# L293D.net
KiCad netlist of a schematic drawn in EAGLE
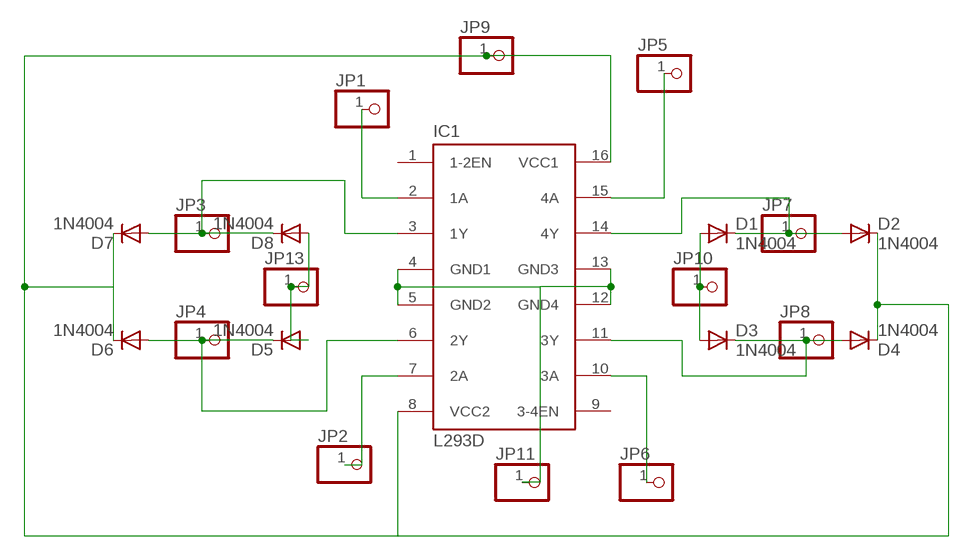
[diagram p0: schematic, sheet 1]

(export (version "E")
  (design (tool "Eeschema 10.0.6"))
  (components
    (comp (ref "D1")
      (value "1N4004")
      (footprint "eagle-import:DO41-10")
      (libsource (lib "eagle-import") (part "1N4004"))
    )
    (comp (ref "D2")
      (value "1N4004")
      (footprint "eagle-import:DO41-10")
      (libsource (lib "eagle-import") (part "1N4004"))
    )
    (comp (ref "D3")
      (value "1N4004")
      (footprint "eagle-import:DO41-10")
      (libsource (lib "eagle-import") (part "1N4004"))
    )
    (comp (ref "D4")
      (value "1N4004")
      (footprint "eagle-import:DO41-10")
      (libsource (lib "eagle-import") (part "1N4004"))
    )
    (comp (ref "D5")
      (value "1N4004")
      (footprint "eagle-import:DO41-10")
      (libsource (lib "eagle-import") (part "1N4004"))
    )
    (comp (ref "D6")
      (value "1N4004")
      (footprint "eagle-import:DO41-10")
      (libsource (lib "eagle-import") (part "1N4004"))
    )
    (comp (ref "D7")
      (value "1N4004")
      (footprint "eagle-import:DO41-10")
      (libsource (lib "eagle-import") (part "1N4004"))
    )
    (comp (ref "D8")
      (value "1N4004")
      (footprint "eagle-import:DO41-10")
      (libsource (lib "eagle-import") (part "1N4004"))
    )
    (comp (ref "IC1")
      (value "L293D")
      (footprint "eagle-import:DIL16")
      (libsource (lib "eagle-import") (part "L293D"))
    )
    (comp (ref "JP1")
      (value "PINHD-1X1")
      (footprint "eagle-import:1X01")
      (libsource (lib "eagle-import") (part "PINHD-1X1"))
    )
    (comp (ref "JP2")
      (value "PINHD-1X1")
      (footprint "eagle-import:1X01")
      (libsource (lib "eagle-import") (part "PINHD-1X1"))
    )
    (comp (ref "JP3")
      (value "PINHD-1X1")
      (footprint "eagle-import:1X01")
      (libsource (lib "eagle-import") (part "PINHD-1X1"))
    )
    (comp (ref "JP4")
      (value "PINHD-1X1")
      (footprint "eagle-import:1X01")
      (libsource (lib "eagle-import") (part "PINHD-1X1"))
    )
    (comp (ref "JP5")
      (value "PINHD-1X1")
      (footprint "eagle-import:1X01")
      (libsource (lib "eagle-import") (part "PINHD-1X1"))
    )
    (comp (ref "JP6")
      (value "PINHD-1X1")
      (footprint "eagle-import:1X01")
      (libsource (lib "eagle-import") (part "PINHD-1X1"))
    )
    (comp (ref "JP7")
      (value "PINHD-1X1")
      (footprint "eagle-import:1X01")
      (libsource (lib "eagle-import") (part "PINHD-1X1"))
    )
    (comp (ref "JP8")
      (value "PINHD-1X1")
      (footprint "eagle-import:1X01")
      (libsource (lib "eagle-import") (part "PINHD-1X1"))
    )
    (comp (ref "JP9")
      (value "PINHD-1X1")
      (footprint "eagle-import:1X01")
      (libsource (lib "eagle-import") (part "PINHD-1X1"))
    )
    (comp (ref "JP10")
      (value "PINHD-1X1")
      (footprint "eagle-import:1X01")
      (libsource (lib "eagle-import") (part "PINHD-1X1"))
    )
    (comp (ref "JP11")
      (value "PINHD-1X1")
      (footprint "eagle-import:1X01")
      (libsource (lib "eagle-import") (part "PINHD-1X1"))
    )
    (comp (ref "JP13")
      (value "PINHD-1X1")
      (footprint "eagle-import:1X01")
      (libsource (lib "eagle-import") (part "PINHD-1X1"))
    )
  )
  (nets
    (net (code "1") (name "Net-(D1-PadA)") (class "Default")
      (node (ref "D1") (pin "A") (pinfunction "A_A") (pintype "passive"))
      (node (ref "D3") (pin "A") (pinfunction "A_A") (pintype "passive"))
      (node (ref "JP10") (pin "1") (pinfunction "1_1") (pintype "passive"))
    )
    (net (code "2") (name "Net-(D5-PadA)") (class "Default")
      (node (ref "D5") (pin "A") (pinfunction "A_A") (pintype "passive"))
      (node (ref "D8") (pin "A") (pinfunction "A_A") (pintype "passive"))
      (node (ref "JP13") (pin "1") (pinfunction "1_1") (pintype "passive"))
    )
    (net (code "3") (name "Net-(D6-PadC)") (class "Default")
      (node (ref "D6") (pin "C") (pinfunction "C_C") (pintype "passive"))
      (node (ref "D7") (pin "C") (pinfunction "C_C") (pintype "passive"))
    )
    (net (code "4") (name "Net-(IC1-1A)") (class "Default")
      (node (ref "IC1") (pin "2") (pinfunction "1A_2") (pintype "input"))
      (node (ref "JP1") (pin "1") (pinfunction "1_1") (pintype "passive"))
    )
    (net (code "5") (name "Net-(IC1-1Y)") (class "Default")
      (node (ref "D7") (pin "A") (pinfunction "A_A") (pintype "passive"))
      (node (ref "D8") (pin "C") (pinfunction "C_C") (pintype "passive"))
      (node (ref "IC1") (pin "3") (pinfunction "1Y_3") (pintype "output"))
      (node (ref "JP3") (pin "1") (pinfunction "1_1") (pintype "passive"))
    )
    (net (code "6") (name "Net-(IC1-2A)") (class "Default")
      (node (ref "IC1") (pin "7") (pinfunction "2A_7") (pintype "input"))
      (node (ref "JP2") (pin "1") (pinfunction "1_1") (pintype "passive"))
    )
    (net (code "7") (name "Net-(IC1-2Y)") (class "Default")
      (node (ref "D5") (pin "C") (pinfunction "C_C") (pintype "passive"))
      (node (ref "D6") (pin "A") (pinfunction "A_A") (pintype "passive"))
      (node (ref "IC1") (pin "6") (pinfunction "2Y_6") (pintype "output"))
      (node (ref "JP4") (pin "1") (pinfunction "1_1") (pintype "passive"))
    )
    (net (code "8") (name "Net-(IC1-3A)") (class "Default")
      (node (ref "IC1") (pin "10") (pinfunction "3A_10") (pintype "input"))
      (node (ref "JP6") (pin "1") (pinfunction "1_1") (pintype "passive"))
    )
    (net (code "9") (name "Net-(IC1-3Y)") (class "Default")
      (node (ref "D3") (pin "C") (pinfunction "C_C") (pintype "passive"))
      (node (ref "D4") (pin "A") (pinfunction "A_A") (pintype "passive"))
      (node (ref "IC1") (pin "11") (pinfunction "3Y_11") (pintype "output"))
      (node (ref "JP8") (pin "1") (pinfunction "1_1") (pintype "passive"))
    )
    (net (code "10") (name "Net-(IC1-4A)") (class "Default")
      (node (ref "IC1") (pin "15") (pinfunction "4A_15") (pintype "input"))
      (node (ref "JP5") (pin "1") (pinfunction "1_1") (pintype "passive"))
    )
    (net (code "11") (name "Net-(IC1-4Y)") (class "Default")
      (node (ref "D1") (pin "C") (pinfunction "C_C") (pintype "passive"))
      (node (ref "D2") (pin "A") (pinfunction "A_A") (pintype "passive"))
      (node (ref "IC1") (pin "14") (pinfunction "4Y_14") (pintype "output"))
      (node (ref "JP7") (pin "1") (pinfunction "1_1") (pintype "passive"))
    )
    (net (code "12") (name "Net-(IC1-GND1)") (class "Default")
      (node (ref "IC1") (pin "12") (pinfunction "GND4_12") (pintype "power_in"))
      (node (ref "IC1") (pin "13") (pinfunction "GND3_13") (pintype "power_in"))
      (node (ref "IC1") (pin "4") (pinfunction "GND1_4") (pintype "power_in"))
      (node (ref "IC1") (pin "5") (pinfunction "GND2_5") (pintype "power_in"))
      (node (ref "JP11") (pin "1") (pinfunction "1_1") (pintype "passive"))
    )
    (net (code "13") (name "Net-(IC1-VCC1)") (class "Default")
      (node (ref "D2") (pin "C") (pinfunction "C_C") (pintype "passive"))
      (node (ref "D4") (pin "C") (pinfunction "C_C") (pintype "passive"))
      (node (ref "IC1") (pin "16") (pinfunction "VCC1_16") (pintype "power_in"))
      (node (ref "IC1") (pin "8") (pinfunction "VCC2_8") (pintype "power_in"))
      (node (ref "JP9") (pin "1") (pinfunction "1_1") (pintype "passive"))
    )
    (net (code "14") (name "unconnected-(IC1-1-2EN-Pad1)") (class "Default")
      (node (ref "IC1") (pin "1") (pinfunction "1-2EN_1") (pintype "input"))
    )
    (net (code "15") (name "unconnected-(IC1-3-4EN-Pad9)") (class "Default")
      (node (ref "IC1") (pin "9") (pinfunction "3-4EN_9") (pintype "input"))
    )
  )
)
